# mini-v1_13-macrofab-rtg.net
KiCad netlist of a schematic drawn in EAGLE
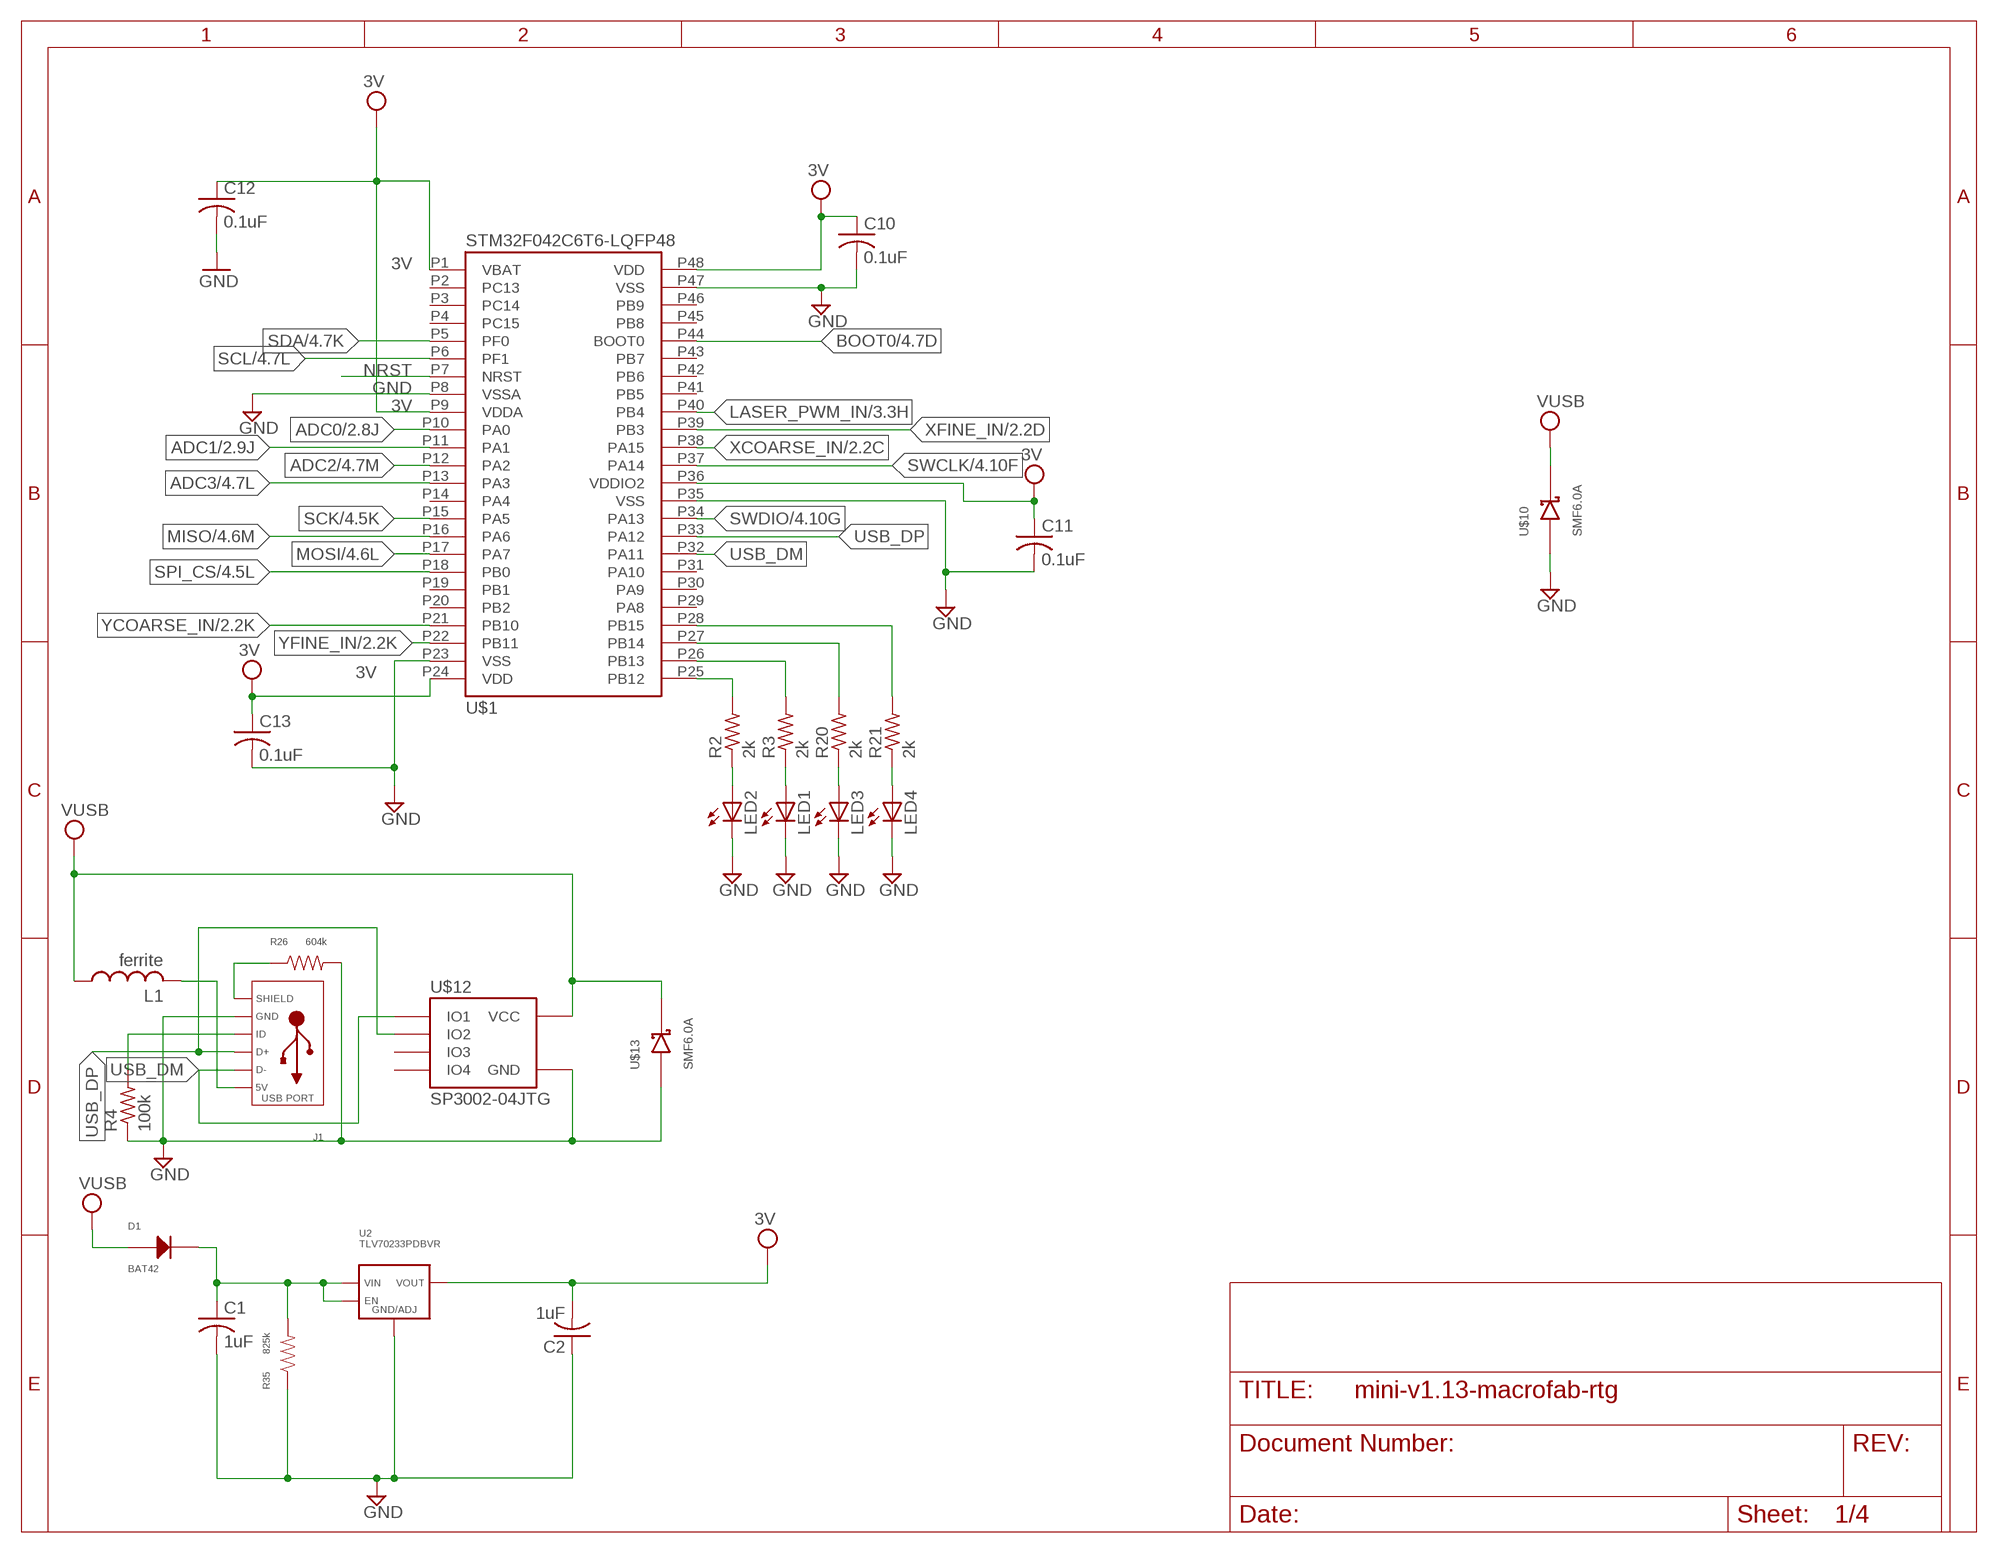
[diagram p0: schematic, sheet 1]
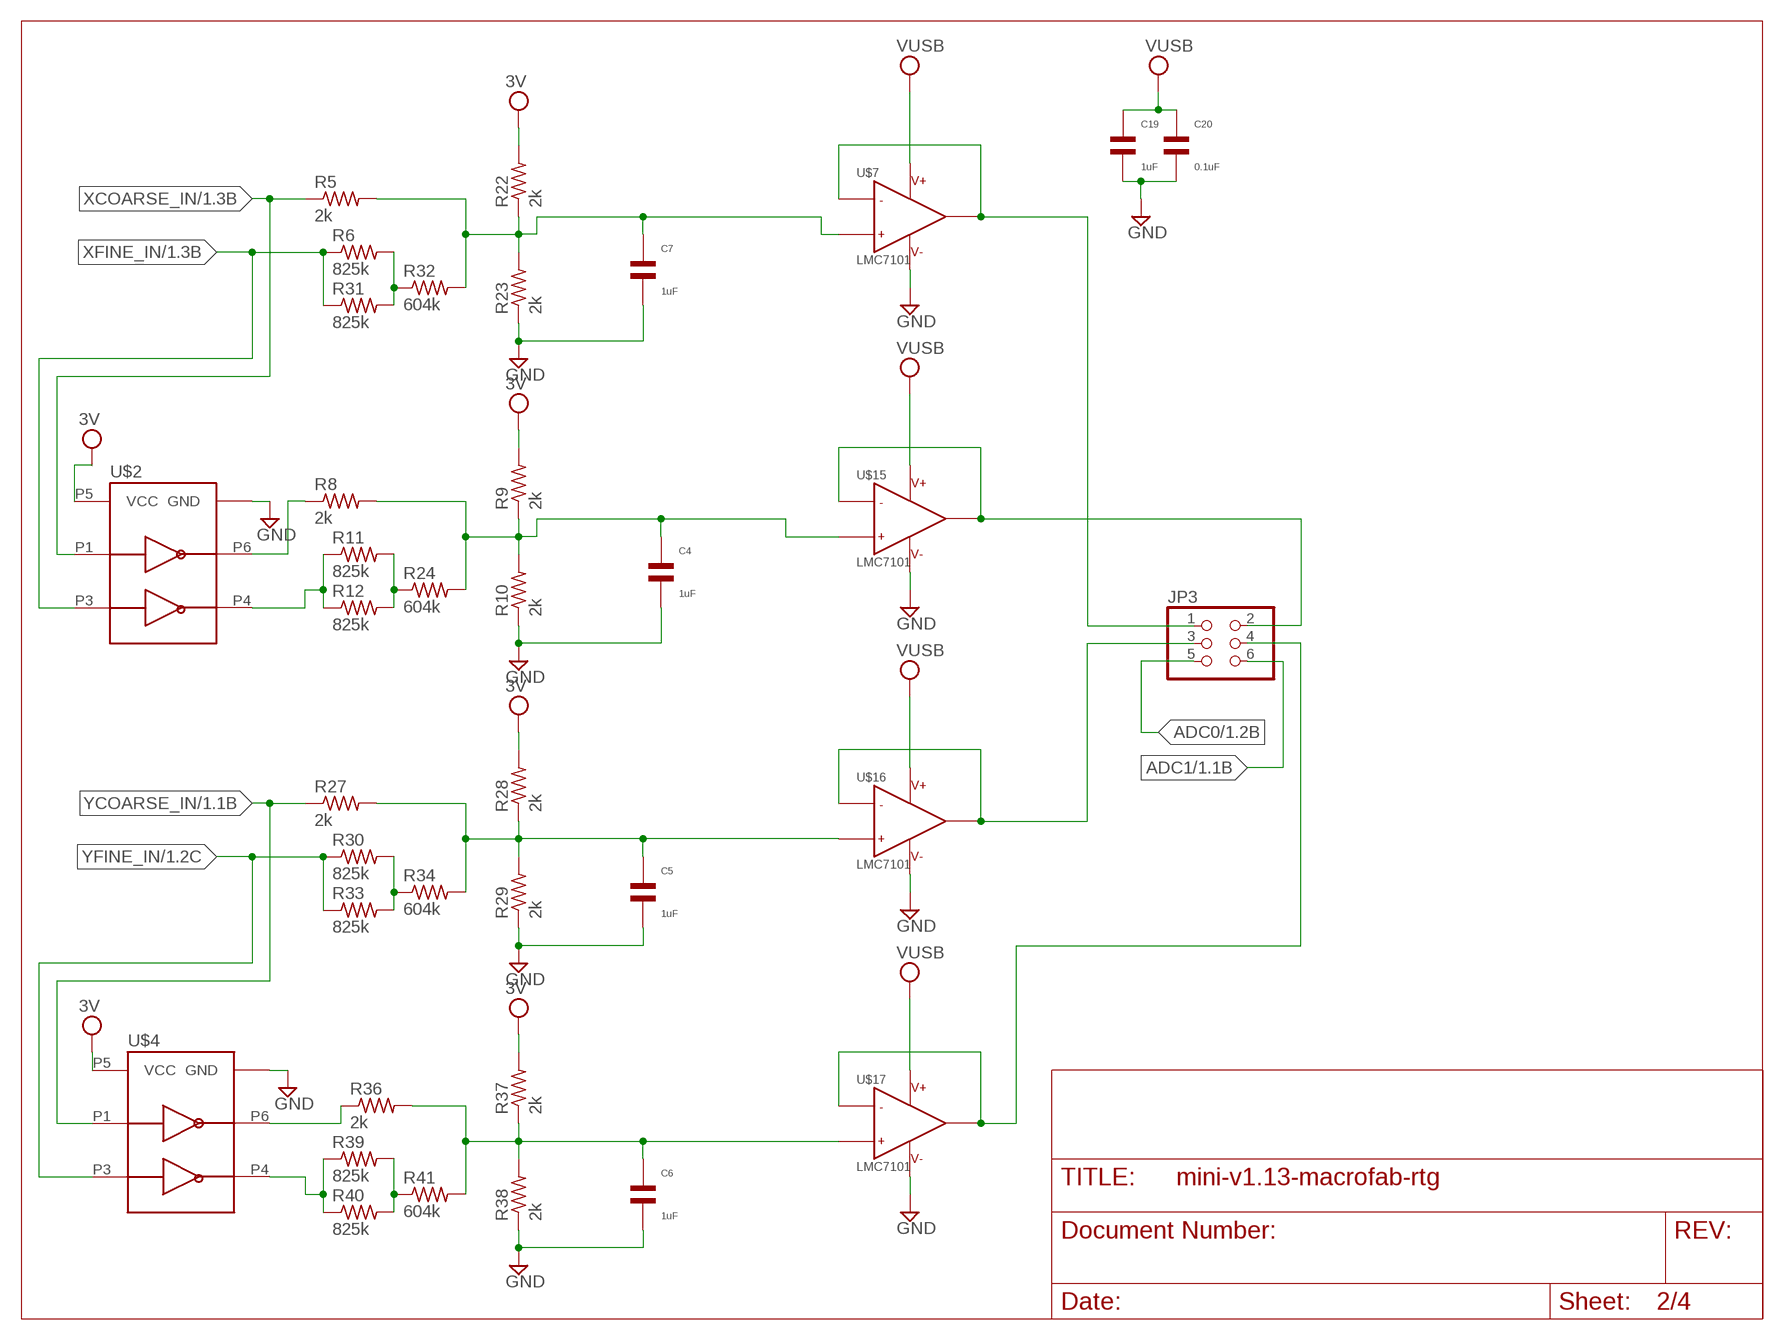
[diagram p1: schematic, sheet 2]
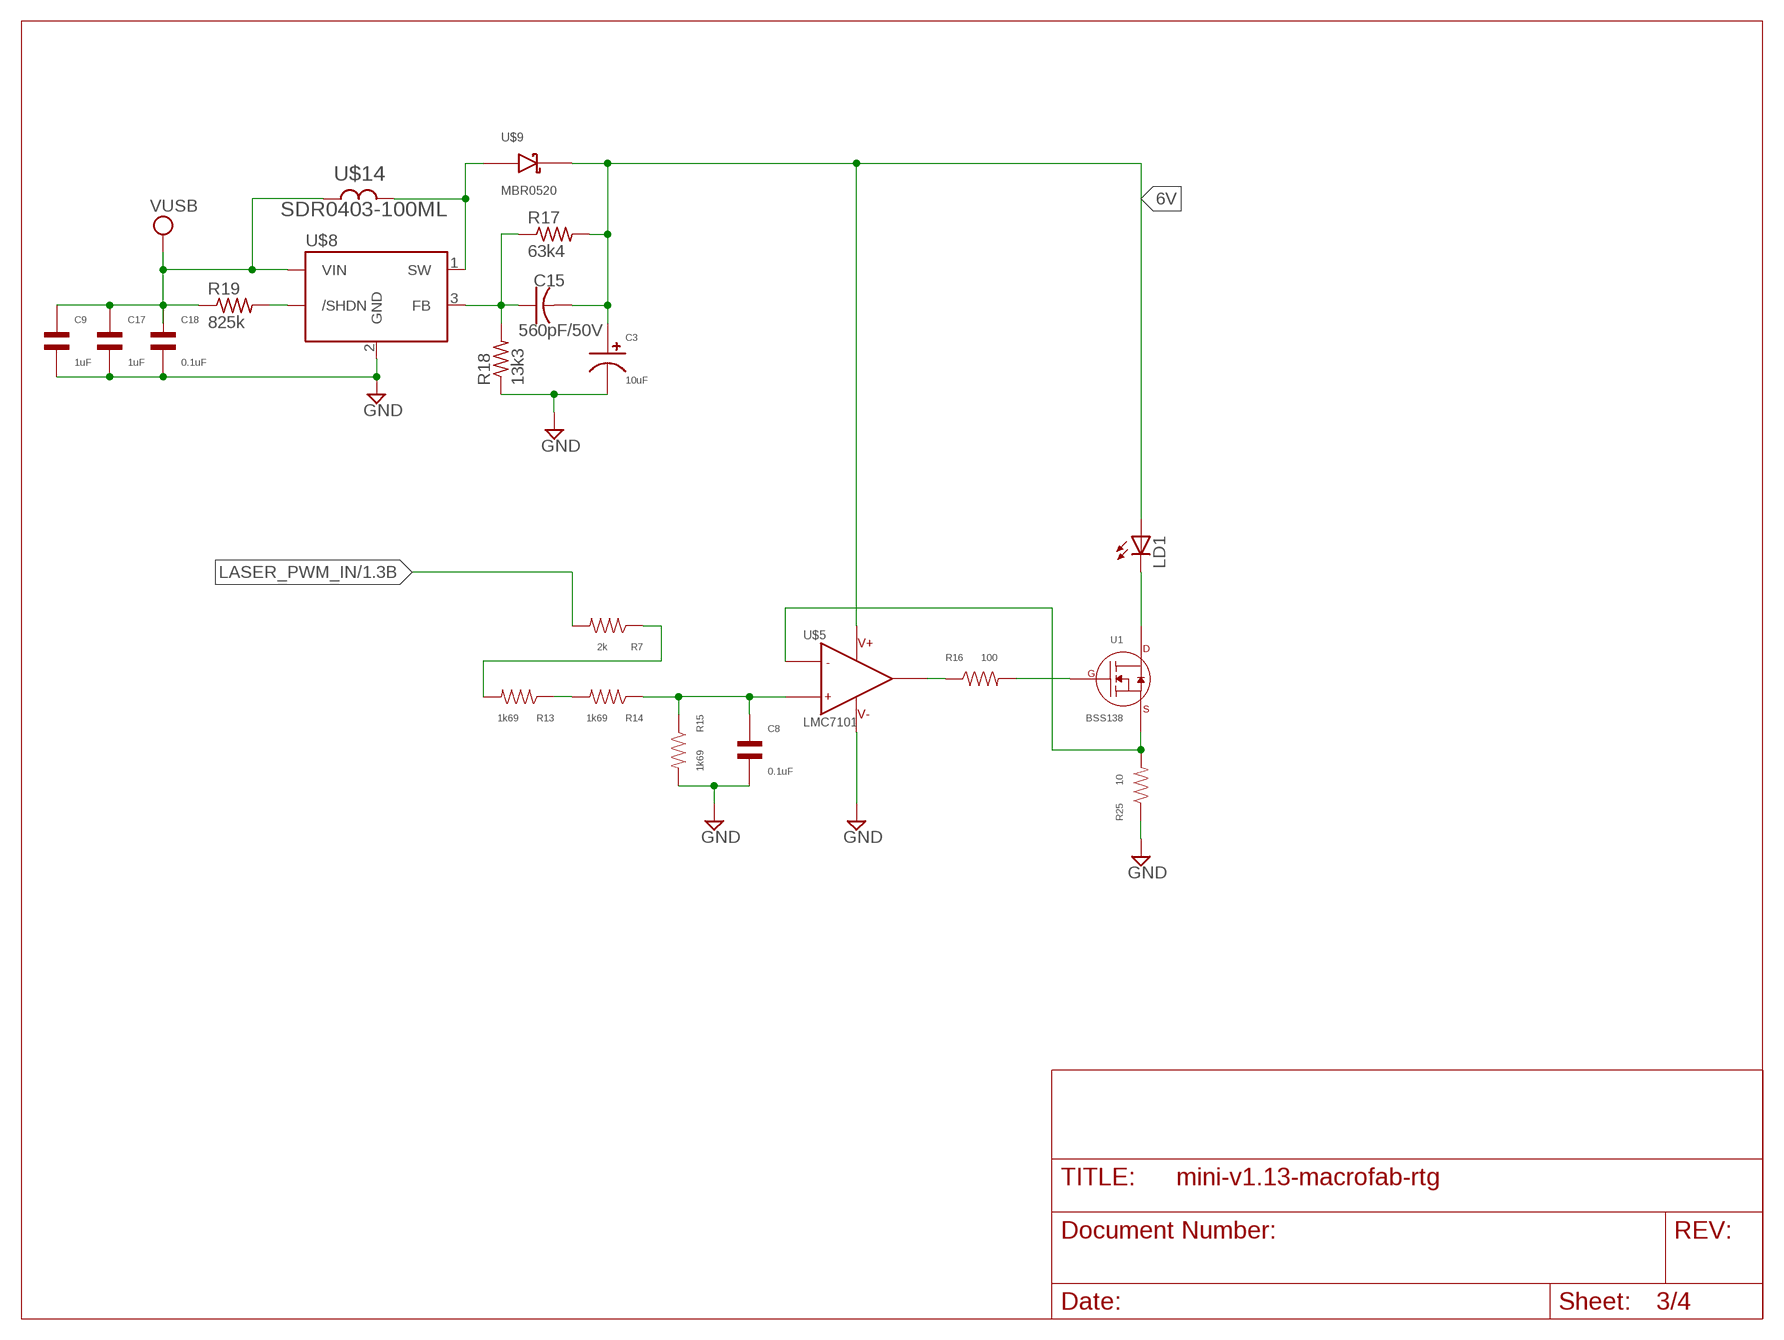
[diagram p2: schematic, sheet 3]
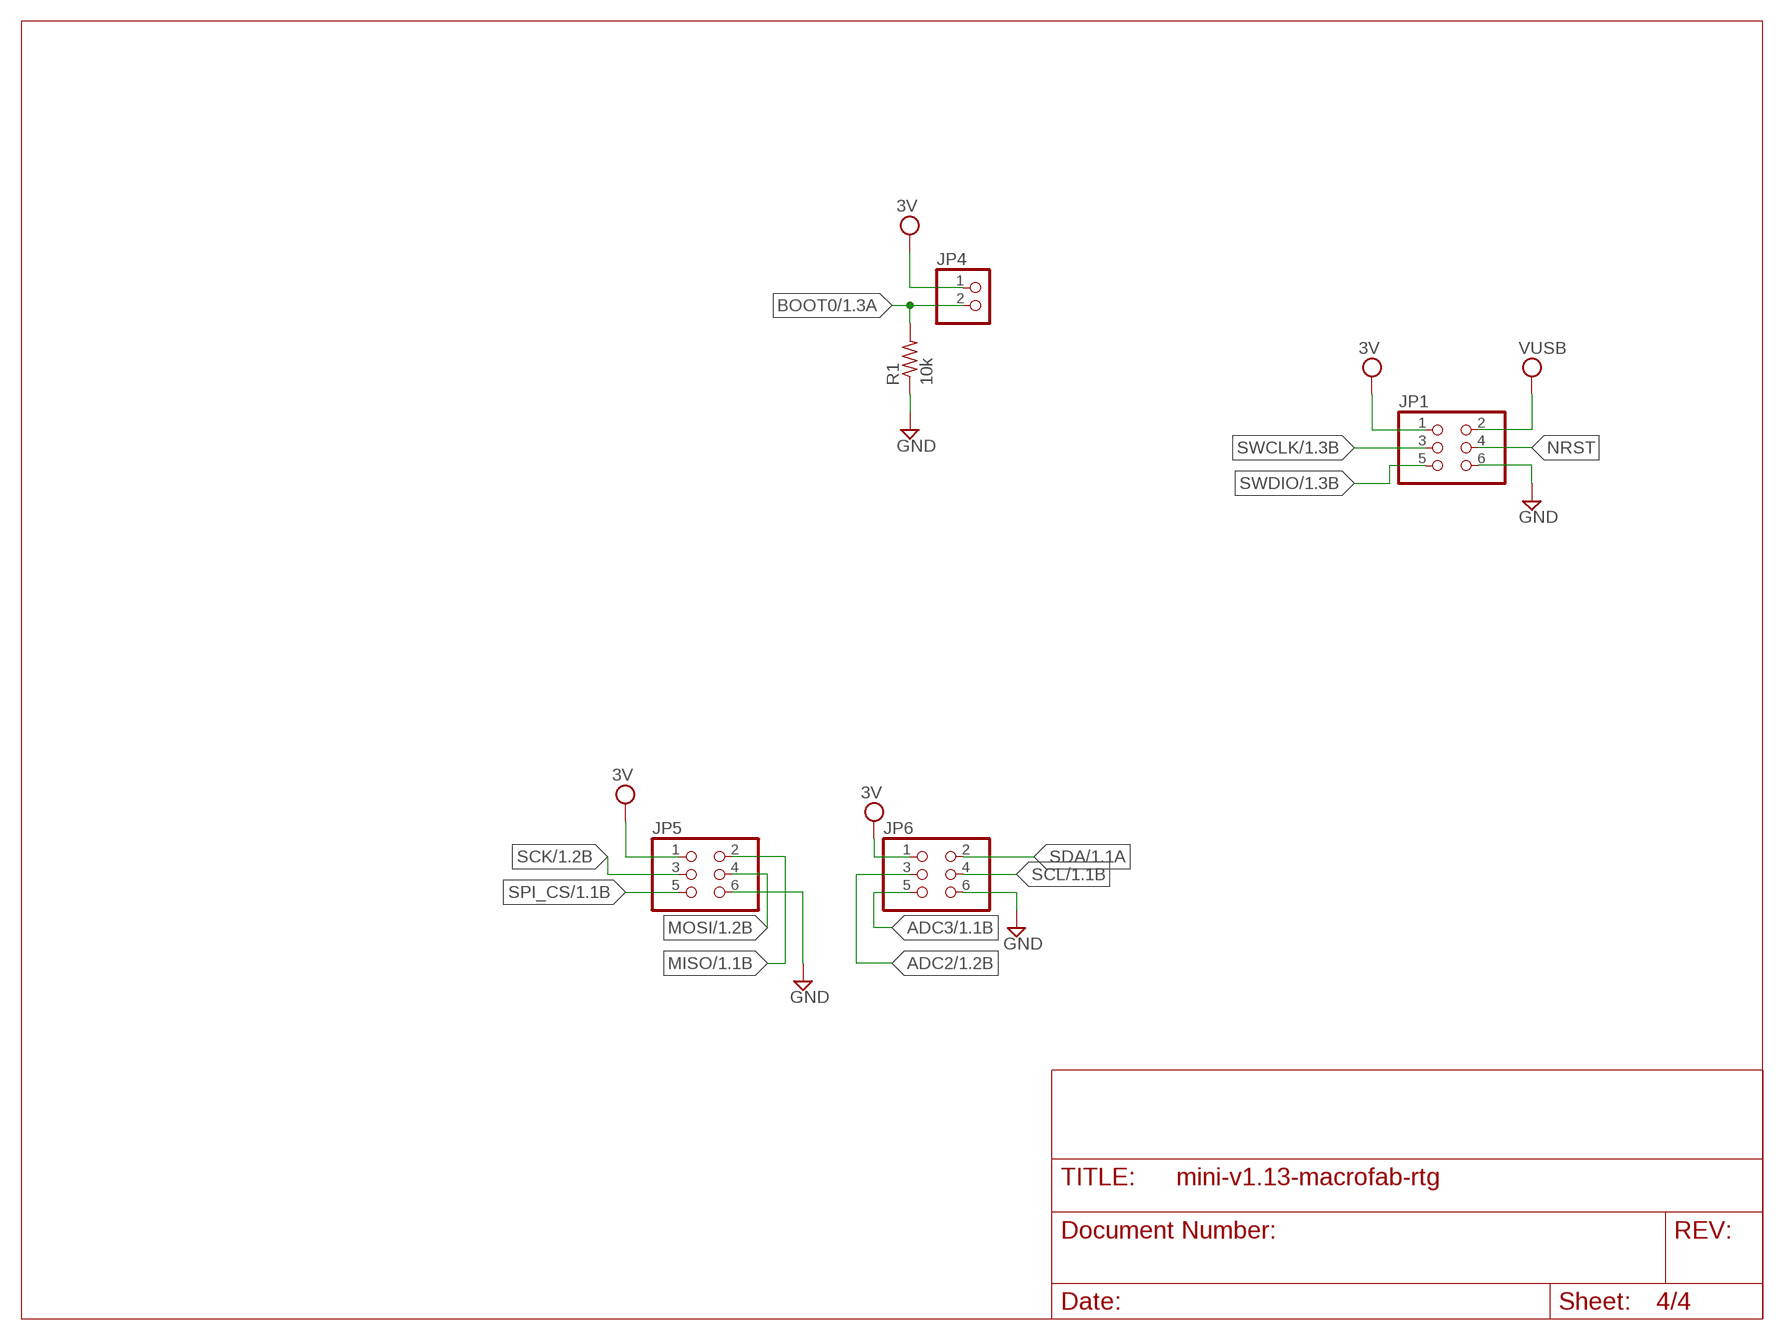
[diagram p3: schematic, sheet 4]

(export (version "E")
  (design (tool "Eeschema 10.0.6"))
  (components
    (comp (ref "C3")
      (value "10uF")
      (footprint "eagle-import:CP4MM")
      (libsource (lib "eagle-import") (part "CAPACITOR_P_4MM"))
    )
    (comp (ref "C8")
      (value "0.1uF")
      (footprint "eagle-import:C0603")
      (libsource (lib "eagle-import") (part "CAPACITOR_NP_0603"))
    )
    (comp (ref "C9")
      (value "1uF")
      (footprint "eagle-import:C0603")
      (libsource (lib "eagle-import") (part "CAPACITOR_NP_0603"))
    )
    (comp (ref "C15")
      (value "560pF/50V")
      (footprint "eagle-import:C0603")
      (libsource (lib "eagle-import") (part "C-USC0603"))
    )
    (comp (ref "C17")
      (value "1uF")
      (footprint "eagle-import:C0603")
      (libsource (lib "eagle-import") (part "CAPACITOR_NP_0603"))
    )
    (comp (ref "C18")
      (value "0.1uF")
      (footprint "eagle-import:C0603")
      (libsource (lib "eagle-import") (part "CAPACITOR_NP_0603"))
    )
    (comp (ref "LD1")
      (value "LASERDIODELD2")
      (footprint "eagle-import:LASERDIODE2")
      (fields (field (name "MPN") "3 x (0552-2-15-15-11-27-10-0)"))
      (libsource (lib "eagle-import") (part "LASERDIODELD2"))
    )
    (comp (ref "R7")
      (value "2k")
      (footprint "eagle-import:R0603")
      (libsource (lib "eagle-import") (part "RESISTOR_0603"))
    )
    (comp (ref "R13")
      (value "1k69")
      (footprint "eagle-import:R0603")
      (libsource (lib "eagle-import") (part "RESISTOR_0603"))
    )
    (comp (ref "R14")
      (value "1k69")
      (footprint "eagle-import:R0603")
      (libsource (lib "eagle-import") (part "RESISTOR_0603"))
    )
    (comp (ref "R15")
      (value "1k69")
      (footprint "eagle-import:R0603")
      (libsource (lib "eagle-import") (part "RESISTOR_0603"))
    )
    (comp (ref "R16")
      (value "100")
      (footprint "eagle-import:R0603")
      (libsource (lib "eagle-import") (part "RESISTOR_0603"))
    )
    (comp (ref "R17")
      (value "63k4")
      (footprint "eagle-import:R0603")
      (libsource (lib "eagle-import") (part "R-US_R0603"))
    )
    (comp (ref "R18")
      (value "13k3")
      (footprint "eagle-import:R0603")
      (libsource (lib "eagle-import") (part "R-US_R0603"))
    )
    (comp (ref "R19")
      (value "825k")
      (footprint "eagle-import:R0603")
      (libsource (lib "eagle-import") (part "R-US_R0603"))
    )
    (comp (ref "R25")
      (value "10")
      (footprint "eagle-import:R0603")
      (libsource (lib "eagle-import") (part "RESISTOR_0603"))
    )
    (comp (ref "U$5")
      (value "LMC7101")
      (footprint "eagle-import:SOT23-5")
      (libsource (lib "eagle-import") (part "OPAMP-SINGLELMC7101"))
    )
    (comp (ref "U$8")
      (value "LMR62014")
      (footprint "eagle-import:SOT23-5")
      (libsource (lib "eagle-import") (part "LMR62014"))
    )
    (comp (ref "U$9")
      (value "MBR0520")
      (footprint "eagle-import:SOD123")
      (libsource (lib "eagle-import") (part "MBR0520"))
    )
    (comp (ref "U$14")
      (value "SDR0403-100ML")
      (footprint "eagle-import:SDR0403")
      (libsource (lib "eagle-import") (part "SDR0403"))
    )
    (comp (ref "U1")
      (value "BSS138")
      (footprint "eagle-import:SOT-23-3")
      (libsource (lib "eagle-import") (part "N-CHANNEL_FET_SOT-23-3"))
    )
    (comp (ref "C1")
      (value "1uF")
      (footprint "eagle-import:C0603")
      (libsource (lib "eagle-import") (part "C-USC0603"))
    )
    (comp (ref "C2")
      (value "1uF")
      (footprint "eagle-import:C0603")
      (libsource (lib "eagle-import") (part "C-USC0603"))
    )
    (comp (ref "C10")
      (value "0.1uF")
      (footprint "eagle-import:C0603")
      (libsource (lib "eagle-import") (part "C-USC0603"))
    )
    (comp (ref "C11")
      (value "0.1uF")
      (footprint "eagle-import:C0603")
      (libsource (lib "eagle-import") (part "C-USC0603"))
    )
    (comp (ref "C12")
      (value "0.1uF")
      (footprint "eagle-import:C0603")
      (libsource (lib "eagle-import") (part "C-USC0603"))
    )
    (comp (ref "C13")
      (value "0.1uF")
      (footprint "eagle-import:C0603")
      (libsource (lib "eagle-import") (part "C-USC0603"))
    )
    (comp (ref "D1")
      (value "BAT42")
      (footprint "eagle-import:SOD-123")
      (libsource (lib "eagle-import") (part "DIODE_SOD-123"))
    )
    (comp (ref "J1")
      (value "USB_MICRO_RIGHT")
      (footprint "eagle-import:MICROUSB-RIGHT")
      (libsource (lib "eagle-import") (part "USB_MICRO_RIGHT"))
    )
    (comp (ref "L1")
      (value "ferrite")
      (footprint "eagle-import:C0603")
      (libsource (lib "eagle-import") (part "L-US"))
    )
    (comp (ref "LED1")
      (value "LEDCHIP-LED0603")
      (footprint "eagle-import:CHIP-LED0603")
      (libsource (lib "eagle-import") (part "LEDCHIP-LED0603"))
    )
    (comp (ref "LED2")
      (value "LEDCHIP-LED0603")
      (footprint "eagle-import:CHIP-LED0603")
      (libsource (lib "eagle-import") (part "LEDCHIP-LED0603"))
    )
    (comp (ref "LED3")
      (value "LEDCHIP-LED0603")
      (footprint "eagle-import:CHIP-LED0603")
      (libsource (lib "eagle-import") (part "LEDCHIP-LED0603"))
    )
    (comp (ref "LED4")
      (value "LEDCHIP-LED0603")
      (footprint "eagle-import:CHIP-LED0603")
      (libsource (lib "eagle-import") (part "LEDCHIP-LED0603"))
    )
    (comp (ref "R2")
      (value "2k")
      (footprint "eagle-import:R0603")
      (libsource (lib "eagle-import") (part "R-US_R0603"))
    )
    (comp (ref "R3")
      (value "2k")
      (footprint "eagle-import:R0603")
      (libsource (lib "eagle-import") (part "R-US_R0603"))
    )
    (comp (ref "R4")
      (value "100k")
      (footprint "eagle-import:R0603")
      (libsource (lib "eagle-import") (part "R-US_R0603"))
    )
    (comp (ref "R20")
      (value "2k")
      (footprint "eagle-import:R0603")
      (libsource (lib "eagle-import") (part "R-US_R0603"))
    )
    (comp (ref "R21")
      (value "2k")
      (footprint "eagle-import:R0603")
      (libsource (lib "eagle-import") (part "R-US_R0603"))
    )
    (comp (ref "R26")
      (value "604k")
      (footprint "eagle-import:R0603")
      (libsource (lib "eagle-import") (part "RESISTOR_0603"))
    )
    (comp (ref "R35")
      (value "825k")
      (footprint "eagle-import:R0603")
      (libsource (lib "eagle-import") (part "RESISTOR_0603"))
    )
    (comp (ref "U$1")
      (value "STM32F042C6T6-LQFP48")
      (footprint "eagle-import:LQFP48")
      (libsource (lib "eagle-import") (part "STM32F042-LQFP48"))
    )
    (comp (ref "U$10")
      (value "SMF6.0A")
      (footprint "eagle-import:SOD123")
      (libsource (lib "eagle-import") (part "MBR0520"))
    )
    (comp (ref "U$12")
      (value "SP3002-04JTG")
      (footprint "eagle-import:SC70-6")
      (libsource (lib "eagle-import") (part "SP3002"))
    )
    (comp (ref "U$13")
      (value "SMF6.0A")
      (footprint "eagle-import:SOD123")
      (libsource (lib "eagle-import") (part "MBR0520"))
    )
    (comp (ref "U2")
      (value "TLV70233PDBVR")
      (footprint "eagle-import:SOT-23-5")
      (libsource (lib "eagle-import") (part "TLV70233PDBVR"))
    )
    (comp (ref "C4")
      (value "1uF")
      (footprint "eagle-import:C0603")
      (libsource (lib "eagle-import") (part "CAPACITOR_NP_0603"))
    )
    (comp (ref "C5")
      (value "1uF")
      (footprint "eagle-import:C0603")
      (libsource (lib "eagle-import") (part "CAPACITOR_NP_0603"))
    )
    (comp (ref "C6")
      (value "1uF")
      (footprint "eagle-import:C0603")
      (libsource (lib "eagle-import") (part "CAPACITOR_NP_0603"))
    )
    (comp (ref "C7")
      (value "1uF")
      (footprint "eagle-import:C0603")
      (libsource (lib "eagle-import") (part "CAPACITOR_NP_0603"))
    )
    (comp (ref "C19")
      (value "1uF")
      (footprint "eagle-import:C0603")
      (libsource (lib "eagle-import") (part "CAPACITOR_NP_0603"))
    )
    (comp (ref "C20")
      (value "0.1uF")
      (footprint "eagle-import:C0603")
      (libsource (lib "eagle-import") (part "CAPACITOR_NP_0603"))
    )
    (comp (ref "JP3")
      (value "PINHD-2X3")
      (footprint "eagle-import:2X03")
      (libsource (lib "eagle-import") (part "PINHD-2X3"))
    )
    (comp (ref "R5")
      (value "2k")
      (footprint "eagle-import:R0603")
      (libsource (lib "eagle-import") (part "R-US_R0603"))
    )
    (comp (ref "R6")
      (value "825k")
      (footprint "eagle-import:R0603")
      (libsource (lib "eagle-import") (part "R-US_R0603"))
    )
    (comp (ref "R8")
      (value "2k")
      (footprint "eagle-import:R0603")
      (libsource (lib "eagle-import") (part "R-US_R0603"))
    )
    (comp (ref "R9")
      (value "2k")
      (footprint "eagle-import:R0603")
      (libsource (lib "eagle-import") (part "R-US_R0603"))
    )
    (comp (ref "R10")
      (value "2k")
      (footprint "eagle-import:R0603")
      (libsource (lib "eagle-import") (part "R-US_R0603"))
    )
    (comp (ref "R11")
      (value "825k")
      (footprint "eagle-import:R0603")
      (libsource (lib "eagle-import") (part "R-US_R0603"))
    )
    (comp (ref "R12")
      (value "825k")
      (footprint "eagle-import:R0603")
      (libsource (lib "eagle-import") (part "R-US_R0603"))
    )
    (comp (ref "R22")
      (value "2k")
      (footprint "eagle-import:R0603")
      (libsource (lib "eagle-import") (part "R-US_R0603"))
    )
    (comp (ref "R23")
      (value "2k")
      (footprint "eagle-import:R0603")
      (libsource (lib "eagle-import") (part "R-US_R0603"))
    )
    (comp (ref "R24")
      (value "604k")
      (footprint "eagle-import:R0603")
      (libsource (lib "eagle-import") (part "R-US_R0603"))
    )
    (comp (ref "R27")
      (value "2k")
      (footprint "eagle-import:R0603")
      (libsource (lib "eagle-import") (part "R-US_R0603"))
    )
    (comp (ref "R28")
      (value "2k")
      (footprint "eagle-import:R0603")
      (libsource (lib "eagle-import") (part "R-US_R0603"))
    )
    (comp (ref "R29")
      (value "2k")
      (footprint "eagle-import:R0603")
      (libsource (lib "eagle-import") (part "R-US_R0603"))
    )
    (comp (ref "R30")
      (value "825k")
      (footprint "eagle-import:R0603")
      (libsource (lib "eagle-import") (part "R-US_R0603"))
    )
    (comp (ref "R31")
      (value "825k")
      (footprint "eagle-import:R0603")
      (libsource (lib "eagle-import") (part "R-US_R0603"))
    )
    (comp (ref "R32")
      (value "604k")
      (footprint "eagle-import:R0603")
      (libsource (lib "eagle-import") (part "R-US_R0603"))
    )
    (comp (ref "R33")
      (value "825k")
      (footprint "eagle-import:R0603")
      (libsource (lib "eagle-import") (part "R-US_R0603"))
    )
    (comp (ref "R34")
      (value "604k")
      (footprint "eagle-import:R0603")
      (libsource (lib "eagle-import") (part "R-US_R0603"))
    )
    (comp (ref "R36")
      (value "2k")
      (footprint "eagle-import:R0603")
      (libsource (lib "eagle-import") (part "R-US_R0603"))
    )
    (comp (ref "R37")
      (value "2k")
      (footprint "eagle-import:R0603")
      (libsource (lib "eagle-import") (part "R-US_R0603"))
    )
    (comp (ref "R38")
      (value "2k")
      (footprint "eagle-import:R0603")
      (libsource (lib "eagle-import") (part "R-US_R0603"))
    )
    (comp (ref "R39")
      (value "825k")
      (footprint "eagle-import:R0603")
      (libsource (lib "eagle-import") (part "R-US_R0603"))
    )
    (comp (ref "R40")
      (value "825k")
      (footprint "eagle-import:R0603")
      (libsource (lib "eagle-import") (part "R-US_R0603"))
    )
    (comp (ref "R41")
      (value "604k")
      (footprint "eagle-import:R0603")
      (libsource (lib "eagle-import") (part "R-US_R0603"))
    )
    (comp (ref "U$2")
      (value "NC7WZ14P6X")
      (footprint "eagle-import:SC70-6")
      (libsource (lib "eagle-import") (part "NC7WZ14P6X"))
    )
    (comp (ref "U$4")
      (value "NC7WZ14P6X")
      (footprint "eagle-import:SC70-6")
      (libsource (lib "eagle-import") (part "NC7WZ14P6X"))
    )
    (comp (ref "U$7")
      (value "LMC7101")
      (footprint "eagle-import:SOT23-5")
      (libsource (lib "eagle-import") (part "LMC7101"))
    )
    (comp (ref "U$15")
      (value "LMC7101")
      (footprint "eagle-import:SOT23-5")
      (libsource (lib "eagle-import") (part "LMC7101"))
    )
    (comp (ref "U$16")
      (value "LMC7101")
      (footprint "eagle-import:SOT23-5")
      (libsource (lib "eagle-import") (part "LMC7101"))
    )
    (comp (ref "U$17")
      (value "LMC7101")
      (footprint "eagle-import:SOT23-5")
      (libsource (lib "eagle-import") (part "LMC7101"))
    )
    (comp (ref "JP1")
      (value "PINHD-2X3")
      (footprint "eagle-import:2X03")
      (libsource (lib "eagle-import") (part "PINHD-2X3"))
    )
    (comp (ref "JP4")
      (value "PINHD-1X2")
      (footprint "eagle-import:1X02")
      (libsource (lib "eagle-import") (part "PINHD-1X2"))
    )
    (comp (ref "JP5")
      (value "PINHD-2X3")
      (footprint "eagle-import:2X03")
      (libsource (lib "eagle-import") (part "PINHD-2X3"))
    )
    (comp (ref "JP6")
      (value "PINHD-2X3")
      (footprint "eagle-import:2X03")
      (libsource (lib "eagle-import") (part "PINHD-2X3"))
    )
    (comp (ref "R1")
      (value "10k")
      (footprint "eagle-import:R0603")
      (libsource (lib "eagle-import") (part "R-US_R0603"))
    )
  )
  (nets
    (net (code "1") (name "3V") (class "Default")
      (node (ref "C10") (pin "1") (pinfunction "1_1") (pintype "passive"))
      (node (ref "C11") (pin "1") (pinfunction "1_1") (pintype "passive"))
      (node (ref "C12") (pin "1") (pinfunction "1_1") (pintype "passive"))
      (node (ref "C13") (pin "1") (pinfunction "1_1") (pintype "passive"))
      (node (ref "C2") (pin "2") (pinfunction "2_2") (pintype "passive"))
      (node (ref "JP1") (pin "1") (pinfunction "1_1") (pintype "passive"))
      (node (ref "JP4") (pin "1") (pinfunction "1_1") (pintype "passive"))
      (node (ref "JP5") (pin "1") (pinfunction "1_1") (pintype "passive"))
      (node (ref "JP6") (pin "1") (pinfunction "1_1") (pintype "passive"))
      (node (ref "R22") (pin "2") (pinfunction "2_2") (pintype "passive"))
      (node (ref "R28") (pin "2") (pinfunction "2_2") (pintype "passive"))
      (node (ref "R37") (pin "2") (pinfunction "2_2") (pintype "passive"))
      (node (ref "R9") (pin "2") (pinfunction "2_2") (pintype "passive"))
      (node (ref "U$1") (pin "P1") (pinfunction "VBAT_P1") (pintype "bidirectional"))
      (node (ref "U$1") (pin "P24") (pinfunction "VDD_P24") (pintype "bidirectional"))
      (node (ref "U$1") (pin "P36") (pinfunction "VDDIO2_P36") (pintype "bidirectional"))
      (node (ref "U$1") (pin "P48") (pinfunction "VDD_P48") (pintype "bidirectional"))
      (node (ref "U$1") (pin "P9") (pinfunction "VDDA_P9") (pintype "bidirectional"))
      (node (ref "U$2") (pin "P5") (pinfunction "VCC_P5") (pintype "power_in"))
      (node (ref "U$4") (pin "P5") (pinfunction "VCC_P5") (pintype "power_in"))
      (node (ref "U2") (pin "P$5") (pinfunction "VOUT_P$5") (pintype "bidirectional"))
    )
    (net (code "2") (name "6V") (class "Default")
      (node (ref "C15") (pin "2") (pinfunction "2_2") (pintype "passive"))
      (node (ref "C3") (pin "P$1") (pinfunction "P$1_P$1") (pintype "passive"))
      (node (ref "LD1") (pin "P$1") (pinfunction "A_P$1") (pintype "passive"))
      (node (ref "R17") (pin "2") (pinfunction "2_2") (pintype "passive"))
      (node (ref "U$5") (pin "2") (pinfunction "V+_2") (pintype "power_in"))
      (node (ref "U$9") (pin "CATHODE") (pinfunction "CATHODE_CATHODE") (pintype "bidirectional"))
    )
    (net (code "3") (name "ADC0") (class "Default")
      (node (ref "JP3") (pin "5") (pinfunction "5_5") (pintype "passive"))
      (node (ref "U$1") (pin "P10") (pinfunction "PA0_P10") (pintype "bidirectional"))
    )
    (net (code "4") (name "ADC1") (class "Default")
      (node (ref "JP3") (pin "6") (pinfunction "6_6") (pintype "passive"))
      (node (ref "U$1") (pin "P11") (pinfunction "PA1_P11") (pintype "bidirectional"))
    )
    (net (code "5") (name "ADC2") (class "Default")
      (node (ref "JP6") (pin "3") (pinfunction "3_3") (pintype "passive"))
      (node (ref "U$1") (pin "P12") (pinfunction "PA2_P12") (pintype "bidirectional"))
    )
    (net (code "6") (name "ADC3") (class "Default")
      (node (ref "JP6") (pin "5") (pinfunction "5_5") (pintype "passive"))
      (node (ref "U$1") (pin "P13") (pinfunction "PA3_P13") (pintype "bidirectional"))
    )
    (net (code "7") (name "BOOT0") (class "Default")
      (node (ref "JP4") (pin "2") (pinfunction "2_2") (pintype "passive"))
      (node (ref "R1") (pin "2") (pinfunction "2_2") (pintype "passive"))
      (node (ref "U$1") (pin "P44") (pinfunction "BOOT0_P44") (pintype "bidirectional"))
    )
    (net (code "8") (name "GND") (class "Default")
      (node (ref "C1") (pin "2") (pinfunction "2_2") (pintype "passive"))
      (node (ref "C10") (pin "2") (pinfunction "2_2") (pintype "passive"))
      (node (ref "C11") (pin "2") (pinfunction "2_2") (pintype "passive"))
      (node (ref "C12") (pin "2") (pinfunction "2_2") (pintype "passive"))
      (node (ref "C13") (pin "2") (pinfunction "2_2") (pintype "passive"))
      (node (ref "C17") (pin "P$2") (pinfunction "P$2_P$2") (pintype "passive"))
      (node (ref "C18") (pin "P$2") (pinfunction "P$2_P$2") (pintype "passive"))
      (node (ref "C19") (pin "P$2") (pinfunction "P$2_P$2") (pintype "passive"))
      (node (ref "C2") (pin "1") (pinfunction "1_1") (pintype "passive"))
      (node (ref "C20") (pin "P$2") (pinfunction "P$2_P$2") (pintype "passive"))
      (node (ref "C3") (pin "P$2") (pinfunction "P$2_P$2") (pintype "passive"))
      (node (ref "C4") (pin "P$2") (pinfunction "P$2_P$2") (pintype "passive"))
      (node (ref "C5") (pin "P$2") (pinfunction "P$2_P$2") (pintype "passive"))
      (node (ref "C6") (pin "P$2") (pinfunction "P$2_P$2") (pintype "passive"))
      (node (ref "C7") (pin "P$2") (pinfunction "P$2_P$2") (pintype "passive"))
      (node (ref "C8") (pin "P$2") (pinfunction "P$2_P$2") (pintype "passive"))
      (node (ref "C9") (pin "P$2") (pinfunction "P$2_P$2") (pintype "passive"))
      (node (ref "J1") (pin "5") (pinfunction "GND_5") (pintype "power_in"))
      (node (ref "JP1") (pin "6") (pinfunction "6_6") (pintype "passive"))
      (node (ref "JP5") (pin "6") (pinfunction "6_6") (pintype "passive"))
      (node (ref "JP6") (pin "6") (pinfunction "6_6") (pintype "passive"))
      (node (ref "LED1") (pin "C") (pinfunction "C_C") (pintype "passive"))
      (node (ref "LED2") (pin "C") (pinfunction "C_C") (pintype "passive"))
      (node (ref "LED3") (pin "C") (pinfunction "C_C") (pintype "passive"))
      (node (ref "LED4") (pin "C") (pinfunction "C_C") (pintype "passive"))
      (node (ref "R1") (pin "1") (pinfunction "1_1") (pintype "passive"))
      (node (ref "R10") (pin "1") (pinfunction "1_1") (pintype "passive"))
      (node (ref "R15") (pin "P$2") (pinfunction "P$2_P$2") (pintype "passive"))
      (node (ref "R18") (pin "1") (pinfunction "1_1") (pintype "passive"))
      (node (ref "R23") (pin "1") (pinfunction "1_1") (pintype "passive"))
      (node (ref "R25") (pin "P$1") (pinfunction "P$1_P$1") (pintype "passive"))
      (node (ref "R26") (pin "P$2") (pinfunction "P$2_P$2") (pintype "passive"))
      (node (ref "R29") (pin "1") (pinfunction "1_1") (pintype "passive"))
      (node (ref "R35") (pin "P$1") (pinfunction "P$1_P$1") (pintype "passive"))
      (node (ref "R38") (pin "1") (pinfunction "1_1") (pintype "passive"))
      (node (ref "R4") (pin "1") (pinfunction "1_1") (pintype "passive"))
      (node (ref "U$1") (pin "P23") (pinfunction "VSS_P23") (pintype "bidirectional"))
      (node (ref "U$1") (pin "P35") (pinfunction "VSS_P35") (pintype "bidirectional"))
      (node (ref "U$1") (pin "P47") (pinfunction "VSS_P47") (pintype "bidirectional"))
      (node (ref "U$1") (pin "P8") (pinfunction "VSSA_P8") (pintype "bidirectional"))
      (node (ref "U$10") (pin "ANODE") (pinfunction "ANODE_ANODE") (pintype "bidirectional"))
      (node (ref "U$12") (pin "P2") (pinfunction "GND_P2") (pintype "power_in"))
      (node (ref "U$13") (pin "ANODE") (pinfunction "ANODE_ANODE") (pintype "bidirectional"))
      (node (ref "U$15") (pin "5") (pinfunction "P5_5") (pintype "power_in"))
      (node (ref "U$16") (pin "5") (pinfunction "P5_5") (pintype "power_in"))
      (node (ref "U$17") (pin "5") (pinfunction "P5_5") (pintype "power_in"))
      (node (ref "U$2") (pin "P2") (pinfunction "GND_P2") (pintype "power_in"))
      (node (ref "U$4") (pin "P2") (pinfunction "GND_P2") (pintype "power_in"))
      (node (ref "U$5") (pin "5") (pinfunction "V-_5") (pintype "power_in"))
      (node (ref "U$7") (pin "5") (pinfunction "P5_5") (pintype "power_in"))
      (node (ref "U$8") (pin "2") (pinfunction "GND_2") (pintype "bidirectional"))
      (node (ref "U2") (pin "P$2") (pinfunction "GND/ADJ_P$2") (pintype "bidirectional"))
    )
    (net (code "9") (name "LASER_PWM_IN") (class "Default")
      (node (ref "R7") (pin "P$2") (pinfunction "P$2_P$2") (pintype "passive"))
      (node (ref "U$1") (pin "P40") (pinfunction "PB4_P40") (pintype "bidirectional"))
    )
    (net (code "10") (name "MISO") (class "Default")
      (node (ref "JP5") (pin "2") (pinfunction "2_2") (pintype "passive"))
      (node (ref "U$1") (pin "P16") (pinfunction "PA6_P16") (pintype "bidirectional"))
    )
    (net (code "11") (name "MOSI") (class "Default")
      (node (ref "JP5") (pin "4") (pinfunction "4_4") (pintype "passive"))
      (node (ref "U$1") (pin "P17") (pinfunction "PA7_P17") (pintype "bidirectional"))
    )
    (net (code "12") (name "NRST") (class "Default")
      (node (ref "JP1") (pin "4") (pinfunction "4_4") (pintype "passive"))
      (node (ref "U$1") (pin "P7") (pinfunction "NRST_P7") (pintype "bidirectional"))
    )
    (net (code "13") (name "Net-(J1-5V)") (class "Default")
      (node (ref "J1") (pin "1") (pinfunction "5V_1") (pintype "power_in"))
      (node (ref "L1") (pin "2") (pinfunction "2_2") (pintype "passive"))
    )
    (net (code "14") (name "Net-(J1-ID)") (class "Default")
      (node (ref "J1") (pin "4") (pinfunction "ID_4") (pintype "bidirectional"))
      (node (ref "R4") (pin "2") (pinfunction "2_2") (pintype "passive"))
    )
    (net (code "15") (name "Net-(J1-SLD-PadS1)") (class "Default")
      (node (ref "J1") (pin "S1") (pinfunction "SLD_S1") (pintype "power_in"))
      (node (ref "J1") (pin "S2") (pinfunction "SLD_S2") (pintype "power_in"))
      (node (ref "J1") (pin "S3") (pinfunction "SLD_S3") (pintype "power_in"))
      (node (ref "J1") (pin "S4") (pinfunction "SLD_S4") (pintype "power_in"))
      (node (ref "J1") (pin "S5") (pinfunction "SLD_S5") (pintype "power_in"))
      (node (ref "J1") (pin "S6") (pinfunction "SLD_S6") (pintype "power_in"))
      (node (ref "R26") (pin "P$1") (pinfunction "P$1_P$1") (pintype "passive"))
    )
    (net (code "16") (name "Net-(LD1-C)") (class "Default")
      (node (ref "LD1") (pin "P$3") (pinfunction "C_P$3") (pintype "passive"))
      (node (ref "U1") (pin "P$3") (pinfunction "DRAIN_P$3") (pintype "bidirectional"))
    )
    (net (code "17") (name "Net-(LED1-PadA)") (class "Default")
      (node (ref "LED1") (pin "A") (pinfunction "A_A") (pintype "passive"))
      (node (ref "R3") (pin "1") (pinfunction "1_1") (pintype "passive"))
    )
    (net (code "18") (name "Net-(LED2-PadA)") (class "Default")
      (node (ref "LED2") (pin "A") (pinfunction "A_A") (pintype "passive"))
      (node (ref "R2") (pin "1") (pinfunction "1_1") (pintype "passive"))
    )
    (net (code "19") (name "Net-(LED3-PadA)") (class "Default")
      (node (ref "LED3") (pin "A") (pinfunction "A_A") (pintype "passive"))
      (node (ref "R20") (pin "1") (pinfunction "1_1") (pintype "passive"))
    )
    (net (code "20") (name "Net-(LED4-PadA)") (class "Default")
      (node (ref "LED4") (pin "A") (pinfunction "A_A") (pintype "passive"))
      (node (ref "R21") (pin "1") (pinfunction "1_1") (pintype "passive"))
    )
    (net (code "21") (name "Net-(R11-Pad2)") (class "Default")
      (node (ref "R11") (pin "2") (pinfunction "2_2") (pintype "passive"))
      (node (ref "R12") (pin "2") (pinfunction "2_2") (pintype "passive"))
      (node (ref "R24") (pin "1") (pinfunction "1_1") (pintype "passive"))
    )
    (net (code "22") (name "Net-(R13-PadP$1)") (class "Default")
      (node (ref "R13") (pin "P$1") (pinfunction "P$1_P$1") (pintype "passive"))
      (node (ref "R14") (pin "P$2") (pinfunction "P$2_P$2") (pintype "passive"))
    )
    (net (code "23") (name "Net-(R13-PadP$2)") (class "Default")
      (node (ref "R13") (pin "P$2") (pinfunction "P$2_P$2") (pintype "passive"))
      (node (ref "R7") (pin "P$1") (pinfunction "P$1_P$1") (pintype "passive"))
    )
    (net (code "24") (name "Net-(R30-Pad2)") (class "Default")
      (node (ref "R30") (pin "2") (pinfunction "2_2") (pintype "passive"))
      (node (ref "R33") (pin "2") (pinfunction "2_2") (pintype "passive"))
      (node (ref "R34") (pin "1") (pinfunction "1_1") (pintype "passive"))
    )
    (net (code "25") (name "Net-(R31-Pad2)") (class "Default")
      (node (ref "R31") (pin "2") (pinfunction "2_2") (pintype "passive"))
      (node (ref "R32") (pin "1") (pinfunction "1_1") (pintype "passive"))
      (node (ref "R6") (pin "2") (pinfunction "2_2") (pintype "passive"))
    )
    (net (code "26") (name "Net-(R39-Pad2)") (class "Default")
      (node (ref "R39") (pin "2") (pinfunction "2_2") (pintype "passive"))
      (node (ref "R40") (pin "2") (pinfunction "2_2") (pintype "passive"))
      (node (ref "R41") (pin "1") (pinfunction "1_1") (pintype "passive"))
    )
    (net (code "27") (name "Net-(U$1-PB12)") (class "Default")
      (node (ref "R2") (pin "2") (pinfunction "2_2") (pintype "passive"))
      (node (ref "U$1") (pin "P25") (pinfunction "PB12_P25") (pintype "bidirectional"))
    )
    (net (code "28") (name "Net-(U$1-PB13)") (class "Default")
      (node (ref "R3") (pin "2") (pinfunction "2_2") (pintype "passive"))
      (node (ref "U$1") (pin "P26") (pinfunction "PB13_P26") (pintype "bidirectional"))
    )
    (net (code "29") (name "Net-(U$1-PB14)") (class "Default")
      (node (ref "R20") (pin "2") (pinfunction "2_2") (pintype "passive"))
      (node (ref "U$1") (pin "P27") (pinfunction "PB14_P27") (pintype "bidirectional"))
    )
    (net (code "30") (name "Net-(U$1-PB15)") (class "Default")
      (node (ref "R21") (pin "2") (pinfunction "2_2") (pintype "passive"))
      (node (ref "U$1") (pin "P28") (pinfunction "PB15_P28") (pintype "bidirectional"))
    )
    (net (code "31") (name "Net-(U$2-Y1)") (class "Default")
      (node (ref "R8") (pin "1") (pinfunction "1_1") (pintype "passive"))
      (node (ref "U$2") (pin "P6") (pinfunction "Y1_P6") (pintype "output"))
    )
    (net (code "32") (name "Net-(U$2-Y2)") (class "Default")
      (node (ref "R11") (pin "1") (pinfunction "1_1") (pintype "passive"))
      (node (ref "R12") (pin "1") (pinfunction "1_1") (pintype "passive"))
      (node (ref "U$2") (pin "P4") (pinfunction "Y2_P4") (pintype "output"))
    )
    (net (code "33") (name "Net-(U$4-Y1)") (class "Default")
      (node (ref "R36") (pin "1") (pinfunction "1_1") (pintype "passive"))
      (node (ref "U$4") (pin "P6") (pinfunction "Y1_P6") (pintype "output"))
    )
    (net (code "34") (name "Net-(U$4-Y2)") (class "Default")
      (node (ref "R39") (pin "1") (pinfunction "1_1") (pintype "passive"))
      (node (ref "R40") (pin "1") (pinfunction "1_1") (pintype "passive"))
      (node (ref "U$4") (pin "P4") (pinfunction "Y2_P4") (pintype "output"))
    )
    (net (code "35") (name "Net-(U$5-IN+)") (class "Default")
      (node (ref "C8") (pin "P$1") (pinfunction "P$1_P$1") (pintype "passive"))
      (node (ref "R14") (pin "P$1") (pinfunction "P$1_P$1") (pintype "passive"))
      (node (ref "R15") (pin "P$1") (pinfunction "P$1_P$1") (pintype "passive"))
      (node (ref "U$5") (pin "3") (pinfunction "IN+_3") (pintype "bidirectional"))
    )
    (net (code "36") (name "Net-(U$5-IN-)") (class "Default")
      (node (ref "R25") (pin "P$2") (pinfunction "P$2_P$2") (pintype "passive"))
      (node (ref "U$5") (pin "4") (pinfunction "IN-_4") (pintype "bidirectional"))
      (node (ref "U1") (pin "P$2") (pinfunction "SOURCE_P$2") (pintype "bidirectional"))
    )
    (net (code "37") (name "Net-(U$5-OUT)") (class "Default")
      (node (ref "R16") (pin "P$1") (pinfunction "P$1_P$1") (pintype "passive"))
      (node (ref "U$5") (pin "1") (pinfunction "OUT_1") (pintype "bidirectional"))
    )
    (net (code "38") (name "Net-(U$7-P1)") (class "Default")
      (node (ref "JP3") (pin "1") (pinfunction "1_1") (pintype "passive"))
      (node (ref "U$7") (pin "1") (pinfunction "P1_1") (pintype "bidirectional"))
      (node (ref "U$7") (pin "4") (pinfunction "P4_4") (pintype "bidirectional"))
    )
    (net (code "39") (name "Net-(U$7-P3)") (class "Default")
      (node (ref "C7") (pin "P$1") (pinfunction "P$1_P$1") (pintype "passive"))
      (node (ref "R22") (pin "1") (pinfunction "1_1") (pintype "passive"))
      (node (ref "R23") (pin "2") (pinfunction "2_2") (pintype "passive"))
      (node (ref "R32") (pin "2") (pinfunction "2_2") (pintype "passive"))
      (node (ref "R5") (pin "2") (pinfunction "2_2") (pintype "passive"))
      (node (ref "U$7") (pin "3") (pinfunction "P3_3") (pintype "bidirectional"))
    )
    (net (code "40") (name "Net-(U$8-FB)") (class "Default")
      (node (ref "C15") (pin "1") (pinfunction "1_1") (pintype "passive"))
      (node (ref "R17") (pin "1") (pinfunction "1_1") (pintype "passive"))
      (node (ref "R18") (pin "2") (pinfunction "2_2") (pintype "passive"))
      (node (ref "U$8") (pin "3") (pinfunction "FB_3") (pintype "bidirectional"))
    )
    (net (code "41") (name "Net-(U$8-SW)") (class "Default")
      (node (ref "U$14") (pin "P$2") (pinfunction "P$2_P$2") (pintype "bidirectional"))
      (node (ref "U$8") (pin "1") (pinfunction "SW_1") (pintype "bidirectional"))
      (node (ref "U$9") (pin "ANODE") (pinfunction "ANODE_ANODE") (pintype "bidirectional"))
    )
    (net (code "42") (name "Net-(U$8-{slash}SHDN)") (class "Default")
      (node (ref "R19") (pin "2") (pinfunction "2_2") (pintype "passive"))
      (node (ref "U$8") (pin "4") (pinfunction "/SHDN_4") (pintype "bidirectional"))
    )
    (net (code "43") (name "Net-(U$15-P1)") (class "Default")
      (node (ref "JP3") (pin "2") (pinfunction "2_2") (pintype "passive"))
      (node (ref "U$15") (pin "1") (pinfunction "P1_1") (pintype "bidirectional"))
      (node (ref "U$15") (pin "4") (pinfunction "P4_4") (pintype "bidirectional"))
    )
    (net (code "44") (name "Net-(U$15-P3)") (class "Default")
      (node (ref "C4") (pin "P$1") (pinfunction "P$1_P$1") (pintype "passive"))
      (node (ref "R10") (pin "2") (pinfunction "2_2") (pintype "passive"))
      (node (ref "R24") (pin "2") (pinfunction "2_2") (pintype "passive"))
      (node (ref "R8") (pin "2") (pinfunction "2_2") (pintype "passive"))
      (node (ref "R9") (pin "1") (pinfunction "1_1") (pintype "passive"))
      (node (ref "U$15") (pin "3") (pinfunction "P3_3") (pintype "bidirectional"))
    )
    (net (code "45") (name "Net-(U$16-P1)") (class "Default")
      (node (ref "JP3") (pin "3") (pinfunction "3_3") (pintype "passive"))
      (node (ref "U$16") (pin "1") (pinfunction "P1_1") (pintype "bidirectional"))
      (node (ref "U$16") (pin "4") (pinfunction "P4_4") (pintype "bidirectional"))
    )
    (net (code "46") (name "Net-(U$16-P3)") (class "Default")
      (node (ref "C5") (pin "P$1") (pinfunction "P$1_P$1") (pintype "passive"))
      (node (ref "R27") (pin "2") (pinfunction "2_2") (pintype "passive"))
      (node (ref "R28") (pin "1") (pinfunction "1_1") (pintype "passive"))
      (node (ref "R29") (pin "2") (pinfunction "2_2") (pintype "passive"))
      (node (ref "R34") (pin "2") (pinfunction "2_2") (pintype "passive"))
      (node (ref "U$16") (pin "3") (pinfunction "P3_3") (pintype "bidirectional"))
    )
    (net (code "47") (name "Net-(U$17-P1)") (class "Default")
      (node (ref "JP3") (pin "4") (pinfunction "4_4") (pintype "passive"))
      (node (ref "U$17") (pin "1") (pinfunction "P1_1") (pintype "bidirectional"))
      (node (ref "U$17") (pin "4") (pinfunction "P4_4") (pintype "bidirectional"))
    )
    (net (code "48") (name "Net-(U$17-P3)") (class "Default")
      (node (ref "C6") (pin "P$1") (pinfunction "P$1_P$1") (pintype "passive"))
      (node (ref "R36") (pin "2") (pinfunction "2_2") (pintype "passive"))
      (node (ref "R37") (pin "1") (pinfunction "1_1") (pintype "passive"))
      (node (ref "R38") (pin "2") (pinfunction "2_2") (pintype "passive"))
      (node (ref "R41") (pin "2") (pinfunction "2_2") (pintype "passive"))
      (node (ref "U$17") (pin "3") (pinfunction "P3_3") (pintype "bidirectional"))
    )
    (net (code "49") (name "Net-(U1-GATE)") (class "Default")
      (node (ref "R16") (pin "P$2") (pinfunction "P$2_P$2") (pintype "passive"))
      (node (ref "U1") (pin "P$1") (pinfunction "GATE_P$1") (pintype "bidirectional"))
    )
    (net (code "50") (name "Net-(U2-EN)") (class "Default")
      (node (ref "C1") (pin "1") (pinfunction "1_1") (pintype "passive"))
      (node (ref "D1") (pin "CATHODE") (pinfunction "CATHODE_CATHODE") (pintype "bidirectional"))
      (node (ref "R35") (pin "P$2") (pinfunction "P$2_P$2") (pintype "passive"))
      (node (ref "U2") (pin "P$1") (pinfunction "VIN_P$1") (pintype "bidirectional"))
      (node (ref "U2") (pin "P$3") (pinfunction "EN_P$3") (pintype "bidirectional"))
    )
    (net (code "51") (name "SCK") (class "Default")
      (node (ref "JP5") (pin "3") (pinfunction "3_3") (pintype "passive"))
      (node (ref "U$1") (pin "P15") (pinfunction "PA5_P15") (pintype "bidirectional"))
    )
    (net (code "52") (name "SCL") (class "Default")
      (node (ref "JP6") (pin "4") (pinfunction "4_4") (pintype "passive"))
      (node (ref "U$1") (pin "P6") (pinfunction "PF1_P6") (pintype "bidirectional"))
    )
    (net (code "53") (name "SDA") (class "Default")
      (node (ref "JP6") (pin "2") (pinfunction "2_2") (pintype "passive"))
      (node (ref "U$1") (pin "P5") (pinfunction "PF0_P5") (pintype "bidirectional"))
    )
    (net (code "54") (name "SPI_CS") (class "Default")
      (node (ref "JP5") (pin "5") (pinfunction "5_5") (pintype "passive"))
      (node (ref "U$1") (pin "P18") (pinfunction "PB0_P18") (pintype "bidirectional"))
    )
    (net (code "55") (name "SWCLK") (class "Default")
      (node (ref "JP1") (pin "3") (pinfunction "3_3") (pintype "passive"))
      (node (ref "U$1") (pin "P37") (pinfunction "PA14_P37") (pintype "bidirectional"))
    )
    (net (code "56") (name "SWDIO") (class "Default")
      (node (ref "JP1") (pin "5") (pinfunction "5_5") (pintype "passive"))
      (node (ref "U$1") (pin "P34") (pinfunction "PA13_P34") (pintype "bidirectional"))
    )
    (net (code "57") (name "USB_DM") (class "Default")
      (node (ref "J1") (pin "2") (pinfunction "D-_2") (pintype "bidirectional"))
      (node (ref "U$1") (pin "P32") (pinfunction "PA11_P32") (pintype "bidirectional"))
      (node (ref "U$12") (pin "P1") (pinfunction "IO1_P1") (pintype "bidirectional"))
    )
    (net (code "58") (name "USB_DP") (class "Default")
      (node (ref "J1") (pin "3") (pinfunction "D+_3") (pintype "bidirectional"))
      (node (ref "U$1") (pin "P33") (pinfunction "PA12_P33") (pintype "bidirectional"))
      (node (ref "U$12") (pin "P3") (pinfunction "IO2_P3") (pintype "bidirectional"))
    )
    (net (code "59") (name "VUSB") (class "Default")
      (node (ref "C17") (pin "P$1") (pinfunction "P$1_P$1") (pintype "passive"))
      (node (ref "C18") (pin "P$1") (pinfunction "P$1_P$1") (pintype "passive"))
      (node (ref "C19") (pin "P$1") (pinfunction "P$1_P$1") (pintype "passive"))
      (node (ref "C20") (pin "P$1") (pinfunction "P$1_P$1") (pintype "passive"))
      (node (ref "C9") (pin "P$1") (pinfunction "P$1_P$1") (pintype "passive"))
      (node (ref "D1") (pin "ANODE") (pinfunction "ANODE_ANODE") (pintype "bidirectional"))
      (node (ref "JP1") (pin "2") (pinfunction "2_2") (pintype "passive"))
      (node (ref "L1") (pin "1") (pinfunction "1_1") (pintype "passive"))
      (node (ref "R19") (pin "1") (pinfunction "1_1") (pintype "passive"))
      (node (ref "U$10") (pin "CATHODE") (pinfunction "CATHODE_CATHODE") (pintype "bidirectional"))
      (node (ref "U$12") (pin "P5") (pinfunction "VCC_P5") (pintype "power_in"))
      (node (ref "U$13") (pin "CATHODE") (pinfunction "CATHODE_CATHODE") (pintype "bidirectional"))
      (node (ref "U$14") (pin "P$1") (pinfunction "P$1_P$1") (pintype "bidirectional"))
      (node (ref "U$15") (pin "2") (pinfunction "P2_2") (pintype "power_in"))
      (node (ref "U$16") (pin "2") (pinfunction "P2_2") (pintype "power_in"))
      (node (ref "U$17") (pin "2") (pinfunction "P2_2") (pintype "power_in"))
      (node (ref "U$7") (pin "2") (pinfunction "P2_2") (pintype "power_in"))
      (node (ref "U$8") (pin "5") (pinfunction "VIN_5") (pintype "bidirectional"))
    )
    (net (code "60") (name "XCOARSE_IN") (class "Default")
      (node (ref "R5") (pin "1") (pinfunction "1_1") (pintype "passive"))
      (node (ref "U$1") (pin "P38") (pinfunction "PA15_P38") (pintype "bidirectional"))
      (node (ref "U$2") (pin "P1") (pinfunction "A1_P1") (pintype "input"))
    )
    (net (code "61") (name "XFINE_IN") (class "Default")
      (node (ref "R31") (pin "1") (pinfunction "1_1") (pintype "passive"))
      (node (ref "R6") (pin "1") (pinfunction "1_1") (pintype "passive"))
      (node (ref "U$1") (pin "P39") (pinfunction "PB3_P39") (pintype "bidirectional"))
      (node (ref "U$2") (pin "P3") (pinfunction "A2_P3") (pintype "input"))
    )
    (net (code "62") (name "YCOARSE_IN") (class "Default")
      (node (ref "R27") (pin "1") (pinfunction "1_1") (pintype "passive"))
      (node (ref "U$1") (pin "P21") (pinfunction "PB10_P21") (pintype "bidirectional"))
      (node (ref "U$4") (pin "P1") (pinfunction "A1_P1") (pintype "input"))
    )
    (net (code "63") (name "YFINE_IN") (class "Default")
      (node (ref "R30") (pin "1") (pinfunction "1_1") (pintype "passive"))
      (node (ref "R33") (pin "1") (pinfunction "1_1") (pintype "passive"))
      (node (ref "U$1") (pin "P22") (pinfunction "PB11_P22") (pintype "bidirectional"))
      (node (ref "U$4") (pin "P3") (pinfunction "A2_P3") (pintype "input"))
    )
    (net (code "64") (name "unconnected-(U$1-PA4-PadP14)") (class "Default")
      (node (ref "U$1") (pin "P14") (pinfunction "PA4_P14") (pintype "bidirectional"))
    )
    (net (code "65") (name "unconnected-(U$1-PA8-PadP29)") (class "Default")
      (node (ref "U$1") (pin "P29") (pinfunction "PA8_P29") (pintype "bidirectional"))
    )
    (net (code "66") (name "unconnected-(U$1-PA9-PadP30)") (class "Default")
      (node (ref "U$1") (pin "P30") (pinfunction "PA9_P30") (pintype "bidirectional"))
    )
    (net (code "67") (name "unconnected-(U$1-PA10-PadP31)") (class "Default")
      (node (ref "U$1") (pin "P31") (pinfunction "PA10_P31") (pintype "bidirectional"))
    )
    (net (code "68") (name "unconnected-(U$1-PB1-PadP19)") (class "Default")
      (node (ref "U$1") (pin "P19") (pinfunction "PB1_P19") (pintype "bidirectional"))
    )
    (net (code "69") (name "unconnected-(U$1-PB2-PadP20)") (class "Default")
      (node (ref "U$1") (pin "P20") (pinfunction "PB2_P20") (pintype "bidirectional"))
    )
    (net (code "70") (name "unconnected-(U$1-PB5-PadP41)") (class "Default")
      (node (ref "U$1") (pin "P41") (pinfunction "PB5_P41") (pintype "bidirectional"))
    )
    (net (code "71") (name "unconnected-(U$1-PB6-PadP42)") (class "Default")
      (node (ref "U$1") (pin "P42") (pinfunction "PB6_P42") (pintype "bidirectional"))
    )
    (net (code "72") (name "unconnected-(U$1-PB7-PadP43)") (class "Default")
      (node (ref "U$1") (pin "P43") (pinfunction "PB7_P43") (pintype "bidirectional"))
    )
    (net (code "73") (name "unconnected-(U$1-PB8-PadP45)") (class "Default")
      (node (ref "U$1") (pin "P45") (pinfunction "PB8_P45") (pintype "bidirectional"))
    )
    (net (code "74") (name "unconnected-(U$1-PB9-PadP46)") (class "Default")
      (node (ref "U$1") (pin "P46") (pinfunction "PB9_P46") (pintype "bidirectional"))
    )
    (net (code "75") (name "unconnected-(U$1-PC13-PadP2)") (class "Default")
      (node (ref "U$1") (pin "P2") (pinfunction "PC13_P2") (pintype "bidirectional"))
    )
    (net (code "76") (name "unconnected-(U$1-PC14-PadP3)") (class "Default")
      (node (ref "U$1") (pin "P3") (pinfunction "PC14_P3") (pintype "bidirectional"))
    )
    (net (code "77") (name "unconnected-(U$1-PC15-PadP4)") (class "Default")
      (node (ref "U$1") (pin "P4") (pinfunction "PC15_P4") (pintype "bidirectional"))
    )
    (net (code "78") (name "unconnected-(U$12-IO3-PadP4)") (class "Default")
      (node (ref "U$12") (pin "P4") (pinfunction "IO3_P4") (pintype "bidirectional"))
    )
    (net (code "79") (name "unconnected-(U$12-IO4-PadP6)") (class "Default")
      (node (ref "U$12") (pin "P6") (pinfunction "IO4_P6") (pintype "bidirectional"))
    )
  )
)
